# GPSModule.net
KiCad netlist of a schematic drawn in EAGLE
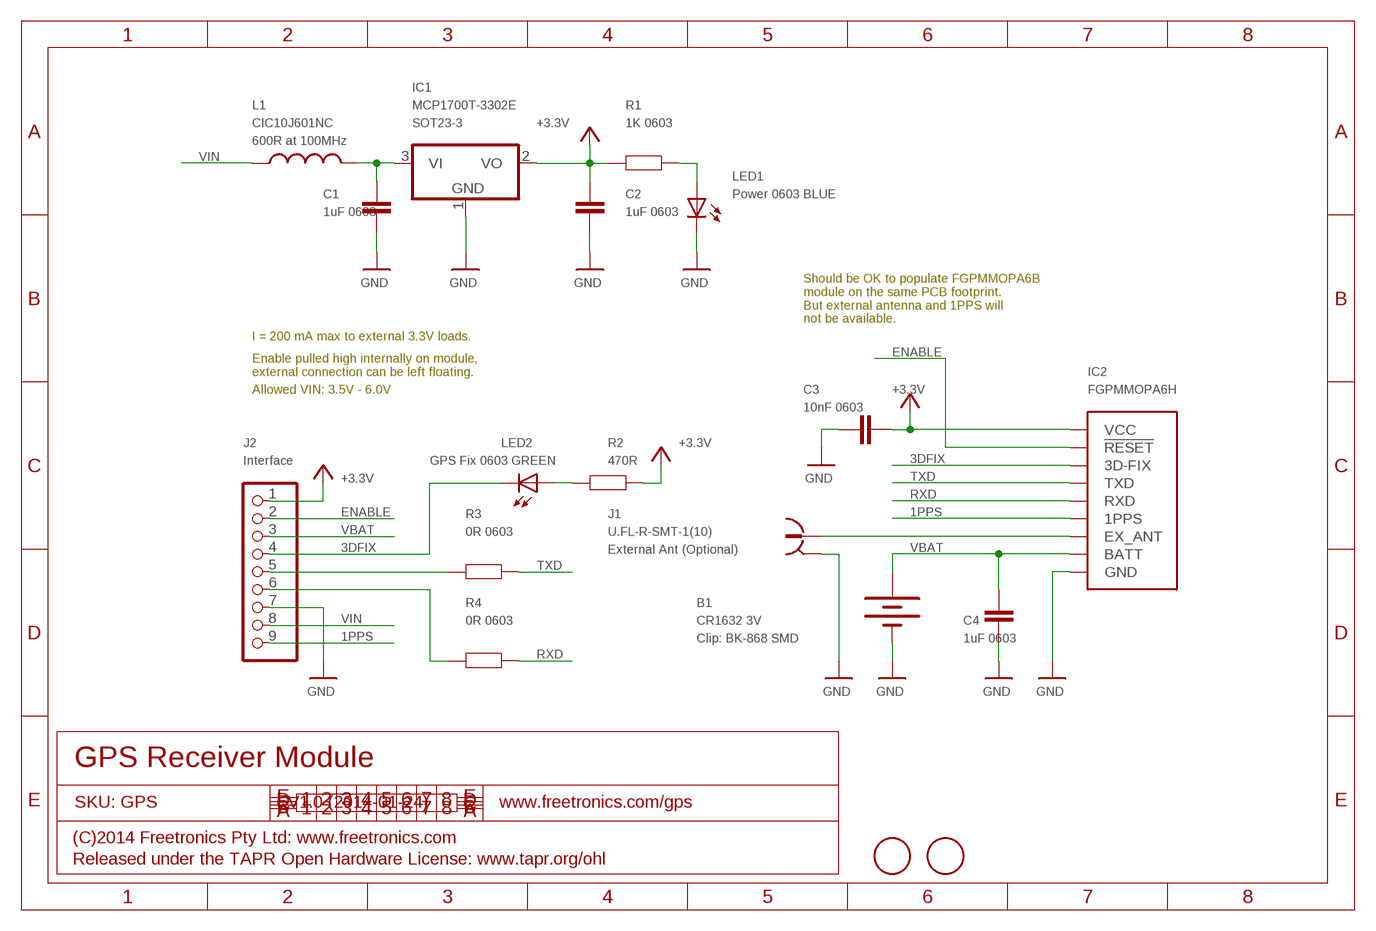
[diagram p0: schematic, sheet 1]

(export (version "E")
  (design (tool "Eeschema 10.0.6"))
  (components
    (comp (ref "B1")
      (value "CR1632 3V")
      (footprint "eagle-import:BATCON_16MM")
      (fields (field (name "FOO") "Clip: BK-868 SMD"))
      (libsource (lib "eagle-import") (part "BATTERY"))
    )
    (comp (ref "C1")
      (value "1uF 0603")
      (footprint "eagle-import:0603")
      (fields (field (name "PACKAGE") "0603"))
      (libsource (lib "eagle-import") (part "CAP0603"))
    )
    (comp (ref "C2")
      (value "1uF 0603")
      (footprint "eagle-import:0603")
      (fields (field (name "PACKAGE") "0603"))
      (libsource (lib "eagle-import") (part "CAP0603"))
    )
    (comp (ref "C3")
      (value "10nF 0603")
      (footprint "eagle-import:0603")
      (fields (field (name "PACKAGE") "0603"))
      (libsource (lib "eagle-import") (part "CAP0603"))
    )
    (comp (ref "C4")
      (value "1uF 0603")
      (footprint "eagle-import:0603")
      (fields (field (name "PACKAGE") "0603"))
      (libsource (lib "eagle-import") (part "CAP0603"))
    )
    (comp (ref "FD1")
      (value "FIDUCIAL")
      (footprint "eagle-import:FIDUCIAL_1MM")
      (libsource (lib "eagle-import") (part "FIDUCIAL"))
    )
    (comp (ref "FD2")
      (value "FIDUCIAL")
      (footprint "eagle-import:FIDUCIAL_1MM")
      (libsource (lib "eagle-import") (part "FIDUCIAL"))
    )
    (comp (ref "IC1")
      (value "MCP1700T-3302E")
      (footprint "eagle-import:SOT23")
      (fields (field (name "PACKAGE") "SOT23-3"))
      (libsource (lib "eagle-import") (part "MCP1703CB"))
    )
    (comp (ref "IC2")
      (value "FGPMMOPA6H")
      (footprint "eagle-import:GPS")
      (libsource (lib "eagle-import") (part "GPS"))
    )
    (comp (ref "J1")
      (value "U.FL-R-SMT-1(10)")
      (footprint "eagle-import:UFL")
      (fields (field (name "NOTE") "External Ant (Optional)"))
      (libsource (lib "eagle-import") (part "UFL"))
    )
    (comp (ref "J2")
      (value "Interface")
      (footprint "eagle-import:1X09")
      (libsource (lib "eagle-import") (part "PINHD-1X9"))
    )
    (comp (ref "L1")
      (value "600R at 100MHz")
      (footprint "eagle-import:0603")
      (fields (field (name "ID") "CIC10J601NC"))
      (libsource (lib "eagle-import") (part "INDUCTOR0603"))
    )
    (comp (ref "LED1")
      (value "Power 0603 BLUE")
      (footprint "eagle-import:LED-0603")
      (fields (field (name "COLOUR") "Blue") (field (name "PACKAGE") "0603"))
      (libsource (lib "eagle-import") (part "LED0603"))
    )
    (comp (ref "LED2")
      (value "GPS Fix 0603 GREEN")
      (footprint "eagle-import:LED-0603")
      (fields (field (name "COLOUR") "Green") (field (name "PACKAGE") "0603"))
      (libsource (lib "eagle-import") (part "LED0603"))
    )
    (comp (ref "R1")
      (value "1K 0603")
      (footprint "eagle-import:0603")
      (fields (field (name "PACKAGE") "0603"))
      (libsource (lib "eagle-import") (part "RESISTOR0603"))
    )
    (comp (ref "R2")
      (value "470R")
      (footprint "eagle-import:0603")
      (fields (field (name "PACKAGE") "0603"))
      (libsource (lib "eagle-import") (part "RESISTOR0603"))
    )
    (comp (ref "R3")
      (value "0R 0603")
      (footprint "eagle-import:0603")
      (fields (field (name "PACKAGE") "0603"))
      (libsource (lib "eagle-import") (part "RESISTOR0603"))
    )
    (comp (ref "R4")
      (value "0R 0603")
      (footprint "eagle-import:0603")
      (fields (field (name "PACKAGE") "0603"))
      (libsource (lib "eagle-import") (part "RESISTOR0603"))
    )
  )
  (nets
    (net (code "1") (name "+3.3V") (class "Default")
      (node (ref "C2") (pin "2") (pinfunction "2_2") (pintype "passive"))
      (node (ref "C3") (pin "1") (pinfunction "1_1") (pintype "passive"))
      (node (ref "IC1") (pin "2") (pinfunction "VO_2") (pintype "passive"))
      (node (ref "IC2") (pin "1") (pinfunction "VCC_1") (pintype "bidirectional"))
      (node (ref "J2") (pin "1") (pinfunction "1_1") (pintype "passive"))
      (node (ref "R1") (pin "2") (pinfunction "2_2") (pintype "passive"))
      (node (ref "R2") (pin "1") (pinfunction "1_1") (pintype "passive"))
    )
    (net (code "2") (name "/1PPS") (class "Default")
      (node (ref "IC2") (pin "13") (pinfunction "1PPS_13") (pintype "bidirectional"))
      (node (ref "J2") (pin "9") (pinfunction "9_9") (pintype "passive"))
    )
    (net (code "3") (name "/3DFIX") (class "Default")
      (node (ref "IC2") (pin "5") (pinfunction "3D-FIX_5") (pintype "bidirectional"))
      (node (ref "J2") (pin "4") (pinfunction "4_4") (pintype "passive"))
      (node (ref "LED2") (pin "C") (pinfunction "C_C") (pintype "passive"))
    )
    (net (code "4") (name "/ENABLE") (class "Default")
      (node (ref "IC2") (pin "2") (pinfunction "~{RESET}_2") (pintype "bidirectional"))
      (node (ref "J2") (pin "2") (pinfunction "2_2") (pintype "passive"))
    )
    (net (code "5") (name "/RXD") (class "Default")
      (node (ref "IC2") (pin "10") (pinfunction "RXD_10") (pintype "bidirectional"))
      (node (ref "R4") (pin "1") (pinfunction "1_1") (pintype "passive"))
    )
    (net (code "6") (name "/TXD") (class "Default")
      (node (ref "IC2") (pin "9") (pinfunction "TXD_9") (pintype "bidirectional"))
      (node (ref "R3") (pin "1") (pinfunction "1_1") (pintype "passive"))
    )
    (net (code "7") (name "/VBAT") (class "Default")
      (node (ref "B1") (pin "PWR@1") (pinfunction "+_PWR@1") (pintype "power_in"))
      (node (ref "C4") (pin "2") (pinfunction "2_2") (pintype "passive"))
      (node (ref "IC2") (pin "4") (pinfunction "BATT_4") (pintype "bidirectional"))
      (node (ref "J2") (pin "3") (pinfunction "3_3") (pintype "passive"))
    )
    (net (code "8") (name "/VIN") (class "Default")
      (node (ref "J2") (pin "8") (pinfunction "8_8") (pintype "passive"))
      (node (ref "L1") (pin "1") (pinfunction "1_1") (pintype "passive"))
    )
    (net (code "9") (name "GND") (class "Default")
      (node (ref "B1") (pin "GND") (pinfunction "-_GND") (pintype "power_in"))
      (node (ref "C1") (pin "1") (pinfunction "1_1") (pintype "passive"))
      (node (ref "C2") (pin "1") (pinfunction "1_1") (pintype "passive"))
      (node (ref "C3") (pin "2") (pinfunction "2_2") (pintype "passive"))
      (node (ref "C4") (pin "1") (pinfunction "1_1") (pintype "passive"))
      (node (ref "IC1") (pin "1") (pinfunction "GND_1") (pintype "passive"))
      (node (ref "IC2") (pin "12") (pinfunction "GND_12") (pintype "bidirectional"))
      (node (ref "IC2") (pin "19") (pinfunction "GND_19") (pintype "bidirectional"))
      (node (ref "IC2") (pin "3") (pinfunction "GND_3") (pintype "bidirectional"))
      (node (ref "IC2") (pin "8") (pinfunction "GND_8") (pintype "bidirectional"))
      (node (ref "J1") (pin "GND") (pinfunction "GND_GND") (pintype "power_in"))
      (node (ref "J1") (pin "GND@1") (pinfunction "GND_GND@1") (pintype "power_in"))
      (node (ref "J2") (pin "7") (pinfunction "7_7") (pintype "passive"))
      (node (ref "LED1") (pin "C") (pinfunction "C_C") (pintype "passive"))
    )
    (net (code "10") (name "Net-(IC1-VI)") (class "Default")
      (node (ref "C1") (pin "2") (pinfunction "2_2") (pintype "passive"))
      (node (ref "IC1") (pin "3") (pinfunction "VI_3") (pintype "input"))
      (node (ref "L1") (pin "2") (pinfunction "2_2") (pintype "passive"))
    )
    (net (code "11") (name "Net-(IC2-EX_ANT)") (class "Default")
      (node (ref "IC2") (pin "11") (pinfunction "EX_ANT_11") (pintype "bidirectional"))
      (node (ref "J1") (pin "SIG") (pinfunction "SIG_SIG") (pintype "passive"))
    )
    (net (code "12") (name "Net-(J2-Pad5)") (class "Default")
      (node (ref "J2") (pin "5") (pinfunction "5_5") (pintype "passive"))
      (node (ref "R3") (pin "2") (pinfunction "2_2") (pintype "passive"))
    )
    (net (code "13") (name "Net-(J2-Pad6)") (class "Default")
      (node (ref "J2") (pin "6") (pinfunction "6_6") (pintype "passive"))
      (node (ref "R4") (pin "2") (pinfunction "2_2") (pintype "passive"))
    )
    (net (code "14") (name "Net-(LED1-PadA)") (class "Default")
      (node (ref "LED1") (pin "A") (pinfunction "A_A") (pintype "passive"))
      (node (ref "R1") (pin "1") (pinfunction "1_1") (pintype "passive"))
    )
    (net (code "15") (name "Net-(LED2-PadA)") (class "Default")
      (node (ref "LED2") (pin "A") (pinfunction "A_A") (pintype "passive"))
      (node (ref "R2") (pin "2") (pinfunction "2_2") (pintype "passive"))
    )
  )
)
